# ArduinoBootLoader-for-1284P-Shield.net
KiCad netlist of a schematic drawn in EasyEDA
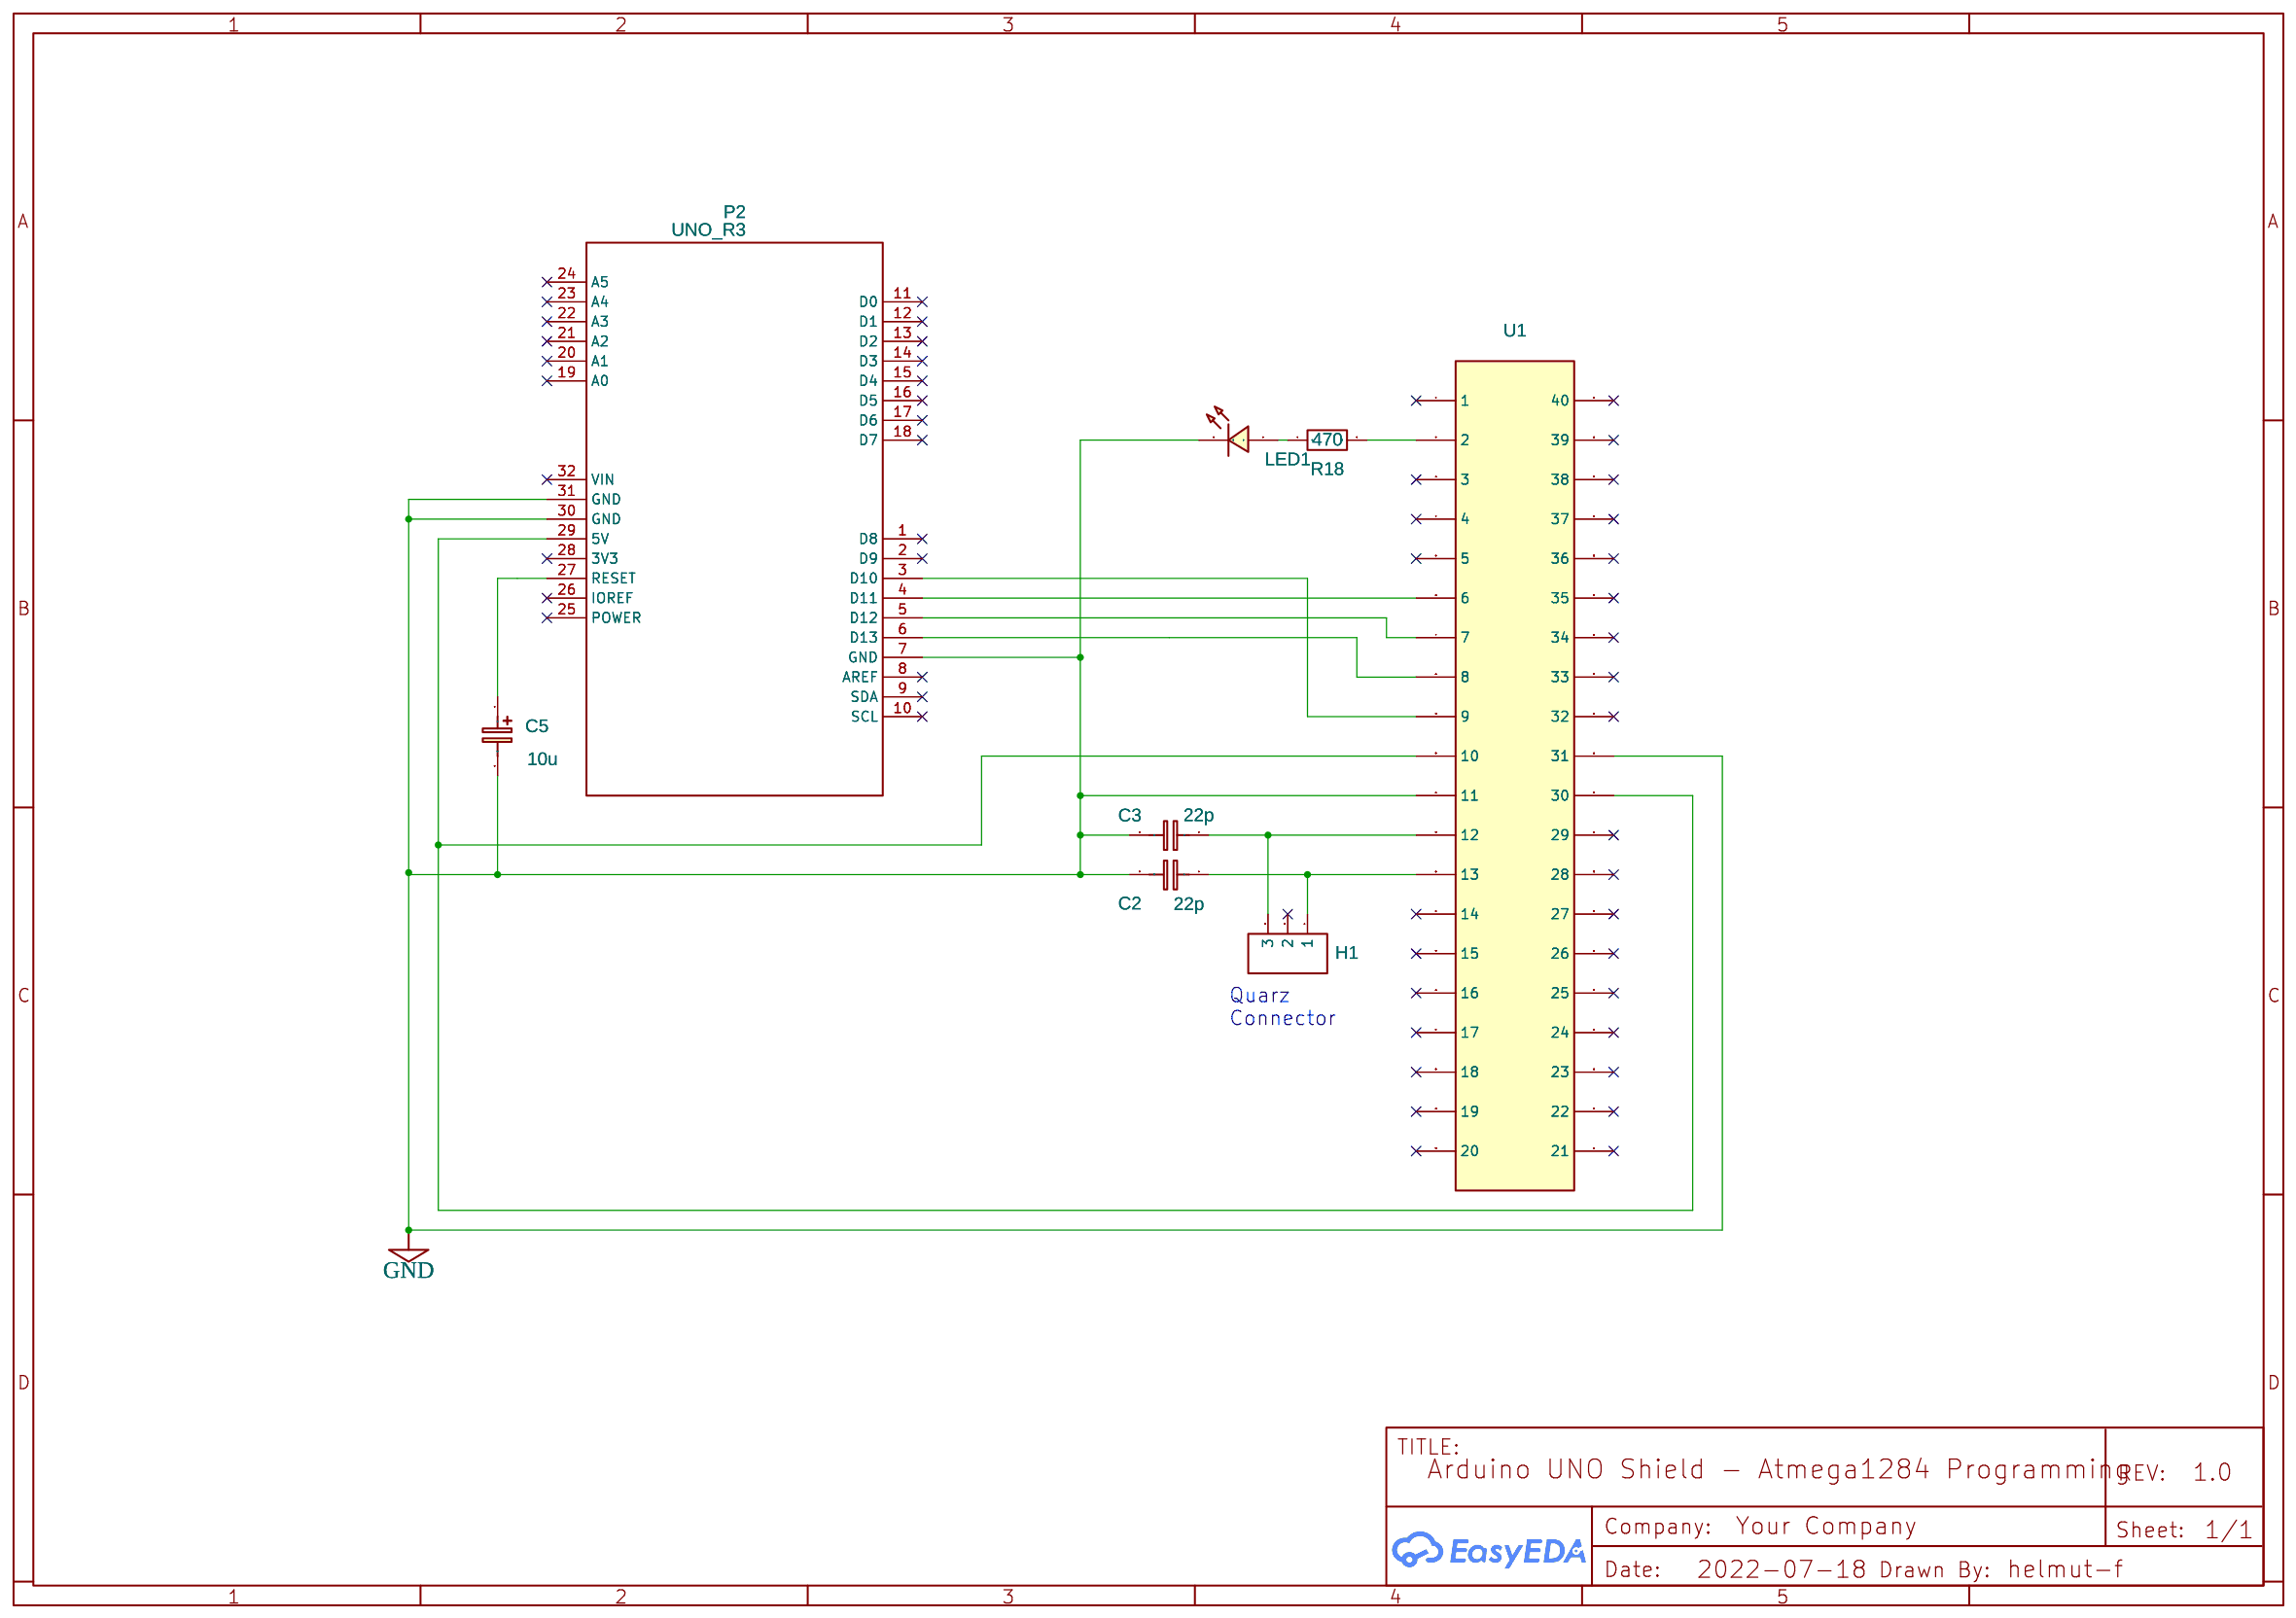
[diagram p0: schematic sheet]

(export (version "E")
  (design (tool "Eeschema 10.0.6"))
  (components
    (comp (ref "C2") (value "22p") (libsource (lib "") (part "C_0603_EU")))
    (comp (ref "C3") (value "22p") (libsource (lib "") (part "C_0603_EU")))
    (comp (ref "C5") (value "10u") (libsource (lib "") (part "CE_TH_D4.0×F1.5_EU")))
    (comp (ref "H1")
      (value "HDR-F-2.54_1x3")
      (fields (field (name "BOM_Supplier Part") "C146690"))
      (libsource (lib "") (part "HDR-F-2.54_1x3"))
    )
    (comp (ref "LED1")
      (value "LED-TH-3mm_R")
      (fields
        (field (name "BOM_Manufacturer Part") "204-10SDRD/S530-A3-L")
        (field (name "BOM_Supplier Part") "C84774")
      )
      (libsource (lib "") (part "LED-TH-3mm_R"))
    )
    (comp (ref "P2") (value "UNO_R3") (libsource (lib "") (part "UNO_R3")))
    (comp (ref "R18") (value "470") (libsource (lib "") (part "R_AXIAL-0.3_EU")))
    (comp (ref "U1")
      (value "DS1009-40AT1WX-0A2")
      (fields (field (name "BOM_Supplier Part") "C72123"))
      (libsource (lib "") (part "DS1009-40AT1WX-0A2"))
    )
  )
  (nets
    (net (code "1") (name "GND") (class "Default")
      (node (ref "C2") (pin "2") (pinfunction "2_2") (pintype "unspecified"))
      (node (ref "C3") (pin "2") (pinfunction "2_2") (pintype "unspecified"))
      (node (ref "C5") (pin "2") (pinfunction "2_2") (pintype "unspecified"))
      (node (ref "LED1") (pin "2") (pinfunction "2_2") (pintype "unspecified"))
      (node (ref "P2") (pin "30") (pinfunction "GND_30") (pintype "unspecified"))
      (node (ref "P2") (pin "31") (pinfunction "GND_31") (pintype "unspecified"))
      (node (ref "P2") (pin "7") (pinfunction "GND_7") (pintype "unspecified"))
      (node (ref "U1") (pin "11") (pinfunction "11_11") (pintype "input"))
      (node (ref "U1") (pin "31") (pinfunction "31_31") (pintype "input"))
    )
    (net (code "2") (name "Net-(C2-Pad1)") (class "Default")
      (node (ref "C2") (pin "1") (pinfunction "1_1") (pintype "unspecified"))
      (node (ref "H1") (pin "1") (pinfunction "1_1") (pintype "input"))
      (node (ref "U1") (pin "13") (pinfunction "13_13") (pintype "input"))
    )
    (net (code "3") (name "Net-(C3-Pad1)") (class "Default")
      (node (ref "C3") (pin "1") (pinfunction "1_1") (pintype "unspecified"))
      (node (ref "H1") (pin "3") (pinfunction "3_3") (pintype "input"))
      (node (ref "U1") (pin "12") (pinfunction "12_12") (pintype "input"))
    )
    (net (code "4") (name "Net-(LED1-Pad1)") (class "Default")
      (node (ref "LED1") (pin "1") (pinfunction "1_1") (pintype "unspecified"))
      (node (ref "R18") (pin "1") (pinfunction "1_1") (pintype "unspecified"))
    )
    (net (code "5") (name "Net-(P2-5V)") (class "Default")
      (node (ref "P2") (pin "29") (pinfunction "5V_29") (pintype "unspecified"))
      (node (ref "U1") (pin "10") (pinfunction "10_10") (pintype "input"))
      (node (ref "U1") (pin "30") (pinfunction "30_30") (pintype "input"))
    )
    (net (code "6") (name "Net-(P2-D10)") (class "Default")
      (node (ref "P2") (pin "3") (pinfunction "D10_3") (pintype "unspecified"))
      (node (ref "U1") (pin "9") (pinfunction "9_9") (pintype "input"))
    )
    (net (code "7") (name "Net-(P2-D11)") (class "Default")
      (node (ref "P2") (pin "4") (pinfunction "D11_4") (pintype "unspecified"))
      (node (ref "U1") (pin "6") (pinfunction "6_6") (pintype "input"))
    )
    (net (code "8") (name "Net-(P2-D12)") (class "Default")
      (node (ref "P2") (pin "5") (pinfunction "D12_5") (pintype "unspecified"))
      (node (ref "U1") (pin "7") (pinfunction "7_7") (pintype "input"))
    )
    (net (code "9") (name "Net-(P2-D13)") (class "Default")
      (node (ref "P2") (pin "6") (pinfunction "D13_6") (pintype "unspecified"))
      (node (ref "U1") (pin "8") (pinfunction "8_8") (pintype "input"))
    )
    (net (code "10") (name "Net-(P2-RESET)") (class "Default")
      (node (ref "C5") (pin "1") (pinfunction "1_1") (pintype "unspecified"))
      (node (ref "P2") (pin "27") (pinfunction "RESET_27") (pintype "unspecified"))
    )
    (net (code "11") (name "Net-(R18-Pad2)") (class "Default")
      (node (ref "R18") (pin "2") (pinfunction "2_2") (pintype "unspecified"))
      (node (ref "U1") (pin "2") (pinfunction "2_2") (pintype "input"))
    )
    (net (code "12") (name "unconnected-(H1-Pad2)") (class "Default")
      (node (ref "H1") (pin "2") (pinfunction "2_2") (pintype "input+no_connect"))
    )
    (net (code "13") (name "unconnected-(P2-3V3-Pad28)") (class "Default")
      (node (ref "P2") (pin "28") (pinfunction "3V3_28") (pintype "unspecified+no_connect"))
    )
    (net (code "14") (name "unconnected-(P2-A0-Pad19)") (class "Default")
      (node (ref "P2") (pin "19") (pinfunction "A0_19") (pintype "unspecified+no_connect"))
    )
    (net (code "15") (name "unconnected-(P2-A1-Pad20)") (class "Default")
      (node (ref "P2") (pin "20") (pinfunction "A1_20") (pintype "unspecified+no_connect"))
    )
    (net (code "16") (name "unconnected-(P2-A2-Pad21)") (class "Default")
      (node (ref "P2") (pin "21") (pinfunction "A2_21") (pintype "unspecified+no_connect"))
    )
    (net (code "17") (name "unconnected-(P2-A3-Pad22)") (class "Default")
      (node (ref "P2") (pin "22") (pinfunction "A3_22") (pintype "unspecified+no_connect"))
    )
    (net (code "18") (name "unconnected-(P2-A4-Pad23)") (class "Default")
      (node (ref "P2") (pin "23") (pinfunction "A4_23") (pintype "unspecified+no_connect"))
    )
    (net (code "19") (name "unconnected-(P2-A5-Pad24)") (class "Default")
      (node (ref "P2") (pin "24") (pinfunction "A5_24") (pintype "unspecified+no_connect"))
    )
    (net (code "20") (name "unconnected-(P2-AREF-Pad8)") (class "Default")
      (node (ref "P2") (pin "8") (pinfunction "AREF_8") (pintype "unspecified+no_connect"))
    )
    (net (code "21") (name "unconnected-(P2-D0-Pad11)") (class "Default")
      (node (ref "P2") (pin "11") (pinfunction "D0_11") (pintype "unspecified+no_connect"))
    )
    (net (code "22") (name "unconnected-(P2-D1-Pad12)") (class "Default")
      (node (ref "P2") (pin "12") (pinfunction "D1_12") (pintype "unspecified+no_connect"))
    )
    (net (code "23") (name "unconnected-(P2-D2-Pad13)") (class "Default")
      (node (ref "P2") (pin "13") (pinfunction "D2_13") (pintype "unspecified+no_connect"))
    )
    (net (code "24") (name "unconnected-(P2-D3-Pad14)") (class "Default")
      (node (ref "P2") (pin "14") (pinfunction "D3_14") (pintype "unspecified+no_connect"))
    )
    (net (code "25") (name "unconnected-(P2-D4-Pad15)") (class "Default")
      (node (ref "P2") (pin "15") (pinfunction "D4_15") (pintype "unspecified+no_connect"))
    )
    (net (code "26") (name "unconnected-(P2-D5-Pad16)") (class "Default")
      (node (ref "P2") (pin "16") (pinfunction "D5_16") (pintype "unspecified+no_connect"))
    )
    (net (code "27") (name "unconnected-(P2-D6-Pad17)") (class "Default")
      (node (ref "P2") (pin "17") (pinfunction "D6_17") (pintype "unspecified+no_connect"))
    )
    (net (code "28") (name "unconnected-(P2-D7-Pad18)") (class "Default")
      (node (ref "P2") (pin "18") (pinfunction "D7_18") (pintype "unspecified+no_connect"))
    )
    (net (code "29") (name "unconnected-(P2-D8-Pad1)") (class "Default")
      (node (ref "P2") (pin "1") (pinfunction "D8_1") (pintype "unspecified+no_connect"))
    )
    (net (code "30") (name "unconnected-(P2-D9-Pad2)") (class "Default")
      (node (ref "P2") (pin "2") (pinfunction "D9_2") (pintype "unspecified+no_connect"))
    )
    (net (code "31") (name "unconnected-(P2-IOREF-Pad26)") (class "Default")
      (node (ref "P2") (pin "26") (pinfunction "IOREF_26") (pintype "unspecified+no_connect"))
    )
    (net (code "32") (name "unconnected-(P2-POWER-Pad25)") (class "Default")
      (node (ref "P2") (pin "25") (pinfunction "POWER_25") (pintype "unspecified+no_connect"))
    )
    (net (code "33") (name "unconnected-(P2-SCL-Pad10)") (class "Default")
      (node (ref "P2") (pin "10") (pinfunction "SCL_10") (pintype "unspecified+no_connect"))
    )
    (net (code "34") (name "unconnected-(P2-SDA-Pad9)") (class "Default")
      (node (ref "P2") (pin "9") (pinfunction "SDA_9") (pintype "unspecified+no_connect"))
    )
    (net (code "35") (name "unconnected-(P2-VIN-Pad32)") (class "Default")
      (node (ref "P2") (pin "32") (pinfunction "VIN_32") (pintype "unspecified+no_connect"))
    )
    (net (code "36") (name "unconnected-(U1-Pad1)") (class "Default")
      (node (ref "U1") (pin "1") (pinfunction "1_1") (pintype "input+no_connect"))
    )
    (net (code "37") (name "unconnected-(U1-Pad3)") (class "Default")
      (node (ref "U1") (pin "3") (pinfunction "3_3") (pintype "input+no_connect"))
    )
    (net (code "38") (name "unconnected-(U1-Pad4)") (class "Default")
      (node (ref "U1") (pin "4") (pinfunction "4_4") (pintype "input+no_connect"))
    )
    (net (code "39") (name "unconnected-(U1-Pad5)") (class "Default")
      (node (ref "U1") (pin "5") (pinfunction "5_5") (pintype "input+no_connect"))
    )
    (net (code "40") (name "unconnected-(U1-Pad14)") (class "Default")
      (node (ref "U1") (pin "14") (pinfunction "14_14") (pintype "input+no_connect"))
    )
    (net (code "41") (name "unconnected-(U1-Pad15)") (class "Default")
      (node (ref "U1") (pin "15") (pinfunction "15_15") (pintype "input+no_connect"))
    )
    (net (code "42") (name "unconnected-(U1-Pad16)") (class "Default")
      (node (ref "U1") (pin "16") (pinfunction "16_16") (pintype "input+no_connect"))
    )
    (net (code "43") (name "unconnected-(U1-Pad17)") (class "Default")
      (node (ref "U1") (pin "17") (pinfunction "17_17") (pintype "input+no_connect"))
    )
    (net (code "44") (name "unconnected-(U1-Pad18)") (class "Default")
      (node (ref "U1") (pin "18") (pinfunction "18_18") (pintype "input+no_connect"))
    )
    (net (code "45") (name "unconnected-(U1-Pad19)") (class "Default")
      (node (ref "U1") (pin "19") (pinfunction "19_19") (pintype "input+no_connect"))
    )
    (net (code "46") (name "unconnected-(U1-Pad20)") (class "Default")
      (node (ref "U1") (pin "20") (pinfunction "20_20") (pintype "input+no_connect"))
    )
    (net (code "47") (name "unconnected-(U1-Pad21)") (class "Default")
      (node (ref "U1") (pin "21") (pinfunction "21_21") (pintype "input+no_connect"))
    )
    (net (code "48") (name "unconnected-(U1-Pad22)") (class "Default")
      (node (ref "U1") (pin "22") (pinfunction "22_22") (pintype "input+no_connect"))
    )
    (net (code "49") (name "unconnected-(U1-Pad23)") (class "Default")
      (node (ref "U1") (pin "23") (pinfunction "23_23") (pintype "input+no_connect"))
    )
    (net (code "50") (name "unconnected-(U1-Pad24)") (class "Default")
      (node (ref "U1") (pin "24") (pinfunction "24_24") (pintype "input+no_connect"))
    )
    (net (code "51") (name "unconnected-(U1-Pad25)") (class "Default")
      (node (ref "U1") (pin "25") (pinfunction "25_25") (pintype "input+no_connect"))
    )
    (net (code "52") (name "unconnected-(U1-Pad26)") (class "Default")
      (node (ref "U1") (pin "26") (pinfunction "26_26") (pintype "input+no_connect"))
    )
    (net (code "53") (name "unconnected-(U1-Pad27)") (class "Default")
      (node (ref "U1") (pin "27") (pinfunction "27_27") (pintype "input+no_connect"))
    )
    (net (code "54") (name "unconnected-(U1-Pad28)") (class "Default")
      (node (ref "U1") (pin "28") (pinfunction "28_28") (pintype "input+no_connect"))
    )
    (net (code "55") (name "unconnected-(U1-Pad29)") (class "Default")
      (node (ref "U1") (pin "29") (pinfunction "29_29") (pintype "input+no_connect"))
    )
    (net (code "56") (name "unconnected-(U1-Pad32)") (class "Default")
      (node (ref "U1") (pin "32") (pinfunction "32_32") (pintype "input+no_connect"))
    )
    (net (code "57") (name "unconnected-(U1-Pad33)") (class "Default")
      (node (ref "U1") (pin "33") (pinfunction "33_33") (pintype "input+no_connect"))
    )
    (net (code "58") (name "unconnected-(U1-Pad34)") (class "Default")
      (node (ref "U1") (pin "34") (pinfunction "34_34") (pintype "input+no_connect"))
    )
    (net (code "59") (name "unconnected-(U1-Pad35)") (class "Default")
      (node (ref "U1") (pin "35") (pinfunction "35_35") (pintype "input+no_connect"))
    )
    (net (code "60") (name "unconnected-(U1-Pad36)") (class "Default")
      (node (ref "U1") (pin "36") (pinfunction "36_36") (pintype "input+no_connect"))
    )
    (net (code "61") (name "unconnected-(U1-Pad37)") (class "Default")
      (node (ref "U1") (pin "37") (pinfunction "37_37") (pintype "input+no_connect"))
    )
    (net (code "62") (name "unconnected-(U1-Pad38)") (class "Default")
      (node (ref "U1") (pin "38") (pinfunction "38_38") (pintype "input+no_connect"))
    )
    (net (code "63") (name "unconnected-(U1-Pad39)") (class "Default")
      (node (ref "U1") (pin "39") (pinfunction "39_39") (pintype "input+no_connect"))
    )
    (net (code "64") (name "unconnected-(U1-Pad40)") (class "Default")
      (node (ref "U1") (pin "40") (pinfunction "40_40") (pintype "input+no_connect"))
    )
  )
)
